# top.net
KiCad netlist of a schematic drawn in Altium Designer
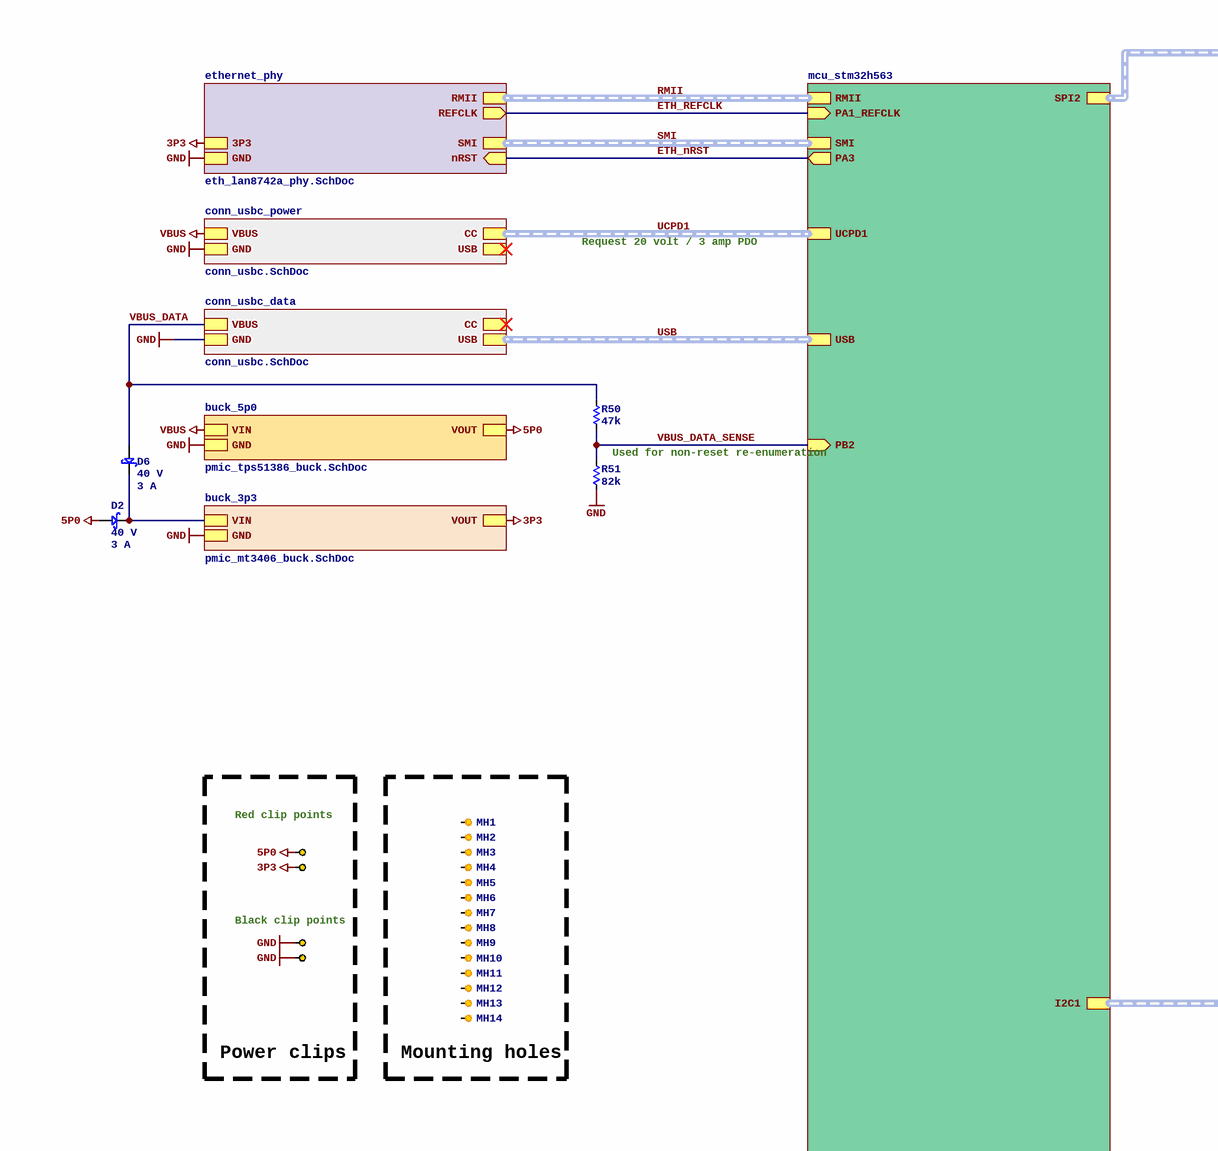
[diagram p0: top.SchDoc, top left]
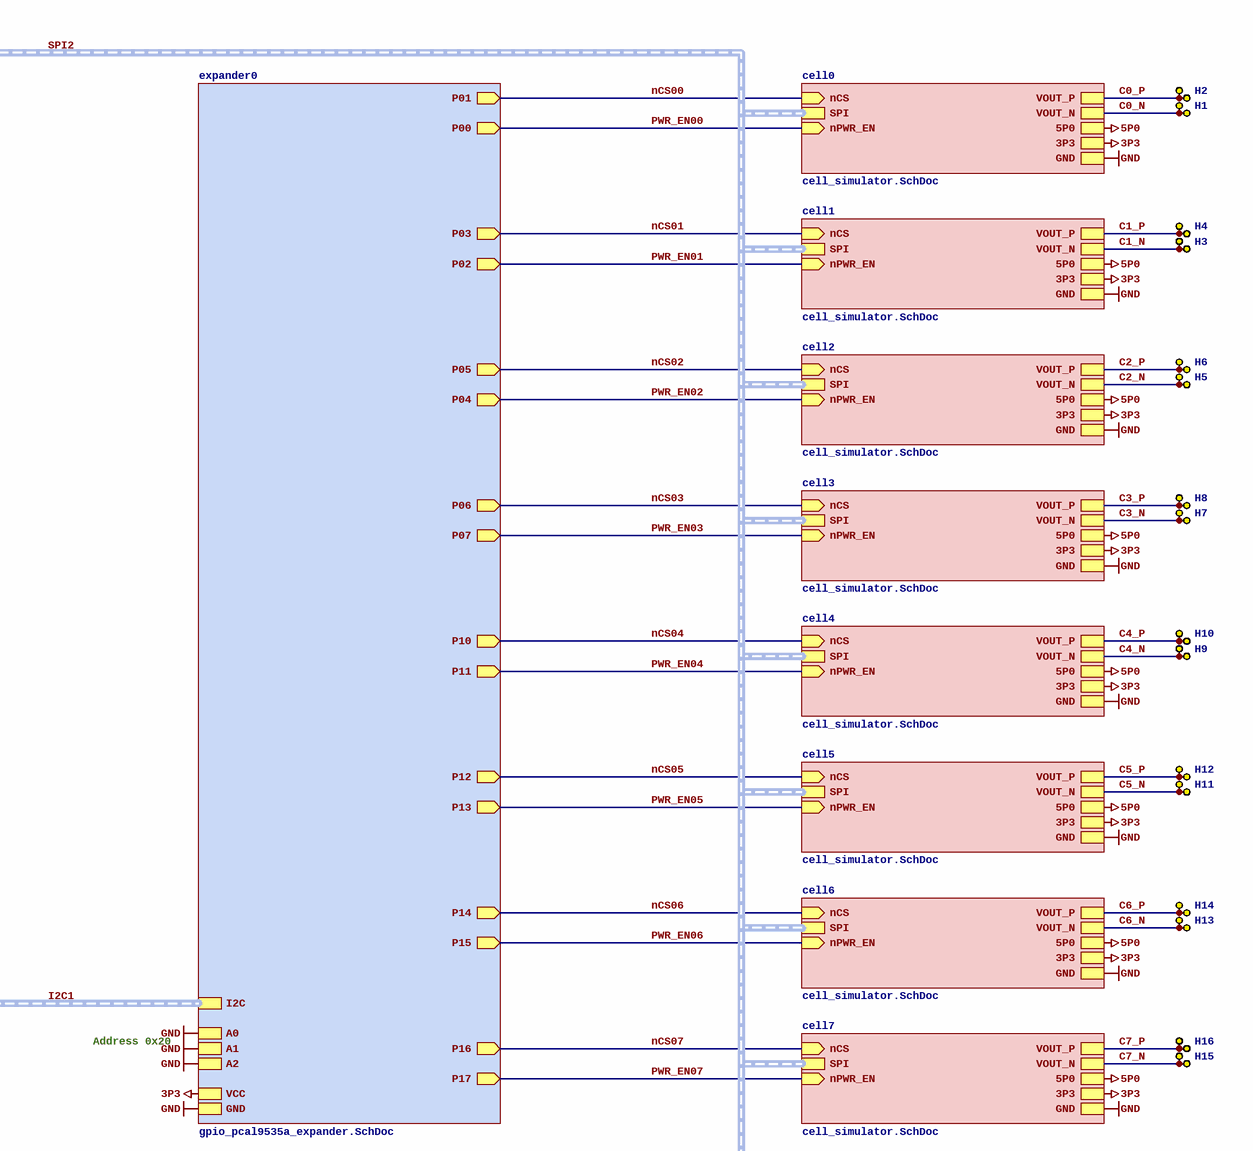
[diagram p1: top.SchDoc, top right]
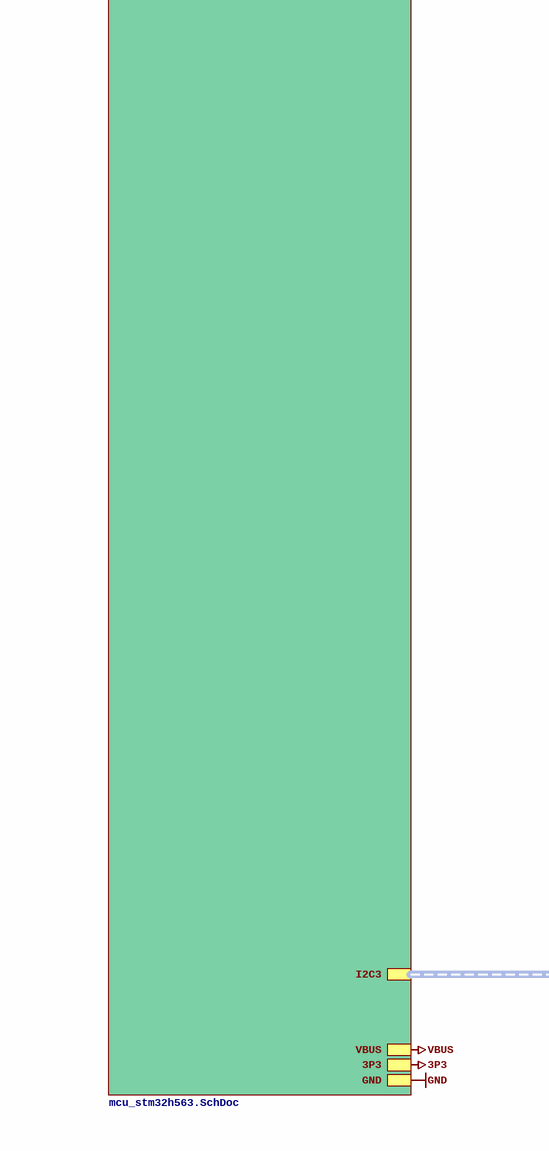
[diagram p2: top.SchDoc, bottom left]
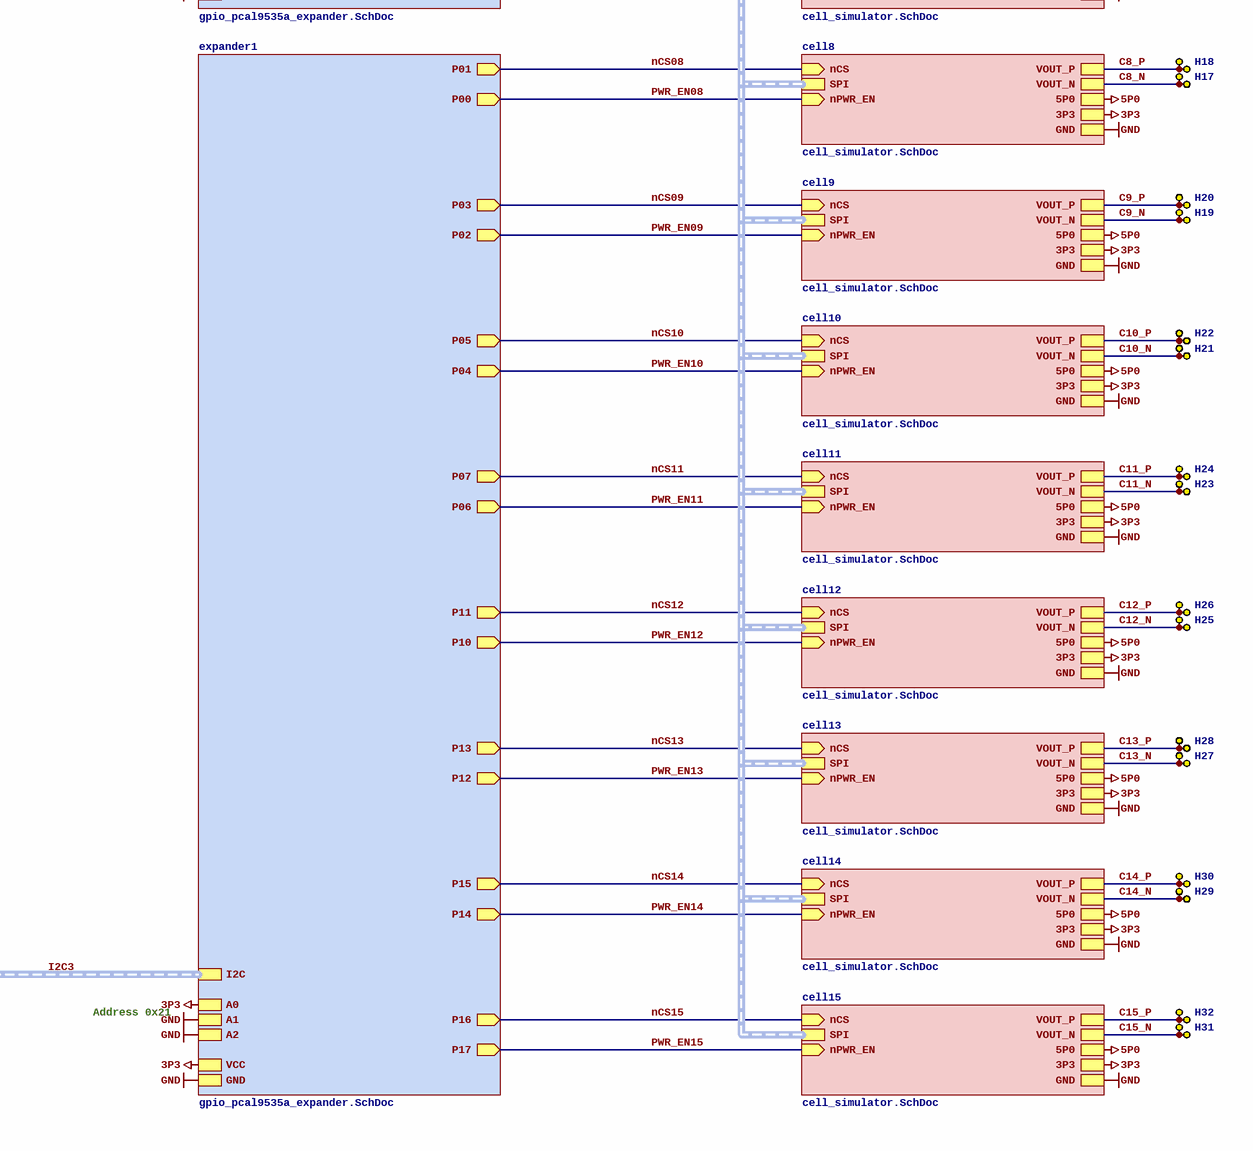
[diagram p3: top.SchDoc, bottom right]

(export (version "E")
  (design (tool "Eeschema 10.0.6"))
  (components
    (comp (ref "D2")
      (value "B340A-13-F")
      (footprint "SMA")
      (description "Rectifier Diode, Schottky, 1 Phase, 1 Element, 3A, 40V V(RRM), Silicon")
      (fields
        (field (name "MANUFACTURER") "Diodes")
        (field (name "VR") "40 V")
        (field (name "CURRENT") "3 A")
      )
      (libsource (lib "database") (part "__template_diode_schottky"))
    )
    (comp (ref "D6")
      (value "B340A-13-F")
      (footprint "SMA")
      (description "Rectifier Diode, Schottky, 1 Phase, 1 Element, 3A, 40V V(RRM), Silicon")
      (fields
        (field (name "MANUFACTURER") "Diodes")
        (field (name "VR") "40 V")
        (field (name "CURRENT") "3 A")
      )
      (libsource (lib "database") (part "__template_diode_schottky"))
    )
    (comp (ref "H1")
      (value "SMTSO20100CTJ")
      (footprint "SINHOO_SMTSO20100CTJ")
      (description "Standoff M2 x 0.4, tin-plated, 10 mm height")
      (fields (field (name "MANUFACTURER") "Sinhoo"))
      (libsource (lib "database") (part "SMTSO20100CTJ"))
    )
    (comp (ref "H2")
      (value "SMTSO20100CTJ")
      (footprint "SINHOO_SMTSO20100CTJ")
      (description "Standoff M2 x 0.4, tin-plated, 10 mm height")
      (fields (field (name "MANUFACTURER") "Sinhoo"))
      (libsource (lib "database") (part "SMTSO20100CTJ"))
    )
    (comp (ref "H3")
      (value "SMTSO20100CTJ")
      (footprint "SINHOO_SMTSO20100CTJ")
      (description "Standoff M2 x 0.4, tin-plated, 10 mm height")
      (fields (field (name "MANUFACTURER") "Sinhoo"))
      (libsource (lib "database") (part "SMTSO20100CTJ"))
    )
    (comp (ref "H4")
      (value "SMTSO20100CTJ")
      (footprint "SINHOO_SMTSO20100CTJ")
      (description "Standoff M2 x 0.4, tin-plated, 10 mm height")
      (fields (field (name "MANUFACTURER") "Sinhoo"))
      (libsource (lib "database") (part "SMTSO20100CTJ"))
    )
    (comp (ref "H5")
      (value "SMTSO20100CTJ")
      (footprint "SINHOO_SMTSO20100CTJ")
      (description "Standoff M2 x 0.4, tin-plated, 10 mm height")
      (fields (field (name "MANUFACTURER") "Sinhoo"))
      (libsource (lib "database") (part "SMTSO20100CTJ"))
    )
    (comp (ref "H6")
      (value "SMTSO20100CTJ")
      (footprint "SINHOO_SMTSO20100CTJ")
      (description "Standoff M2 x 0.4, tin-plated, 10 mm height")
      (fields (field (name "MANUFACTURER") "Sinhoo"))
      (libsource (lib "database") (part "SMTSO20100CTJ"))
    )
    (comp (ref "H7")
      (value "SMTSO20100CTJ")
      (footprint "SINHOO_SMTSO20100CTJ")
      (description "Standoff M2 x 0.4, tin-plated, 10 mm height")
      (fields (field (name "MANUFACTURER") "Sinhoo"))
      (libsource (lib "database") (part "SMTSO20100CTJ"))
    )
    (comp (ref "H8")
      (value "SMTSO20100CTJ")
      (footprint "SINHOO_SMTSO20100CTJ")
      (description "Standoff M2 x 0.4, tin-plated, 10 mm height")
      (fields (field (name "MANUFACTURER") "Sinhoo"))
      (libsource (lib "database") (part "SMTSO20100CTJ"))
    )
    (comp (ref "H9")
      (value "SMTSO20100CTJ")
      (footprint "SINHOO_SMTSO20100CTJ")
      (description "Standoff M2 x 0.4, tin-plated, 10 mm height")
      (fields (field (name "MANUFACTURER") "Sinhoo"))
      (libsource (lib "database") (part "SMTSO20100CTJ"))
    )
    (comp (ref "H10")
      (value "SMTSO20100CTJ")
      (footprint "SINHOO_SMTSO20100CTJ")
      (description "Standoff M2 x 0.4, tin-plated, 10 mm height")
      (fields (field (name "MANUFACTURER") "Sinhoo"))
      (libsource (lib "database") (part "SMTSO20100CTJ"))
    )
    (comp (ref "H11")
      (value "SMTSO20100CTJ")
      (footprint "SINHOO_SMTSO20100CTJ")
      (description "Standoff M2 x 0.4, tin-plated, 10 mm height")
      (fields (field (name "MANUFACTURER") "Sinhoo"))
      (libsource (lib "database") (part "SMTSO20100CTJ"))
    )
    (comp (ref "H12")
      (value "SMTSO20100CTJ")
      (footprint "SINHOO_SMTSO20100CTJ")
      (description "Standoff M2 x 0.4, tin-plated, 10 mm height")
      (fields (field (name "MANUFACTURER") "Sinhoo"))
      (libsource (lib "database") (part "SMTSO20100CTJ"))
    )
    (comp (ref "H13")
      (value "SMTSO20100CTJ")
      (footprint "SINHOO_SMTSO20100CTJ")
      (description "Standoff M2 x 0.4, tin-plated, 10 mm height")
      (fields (field (name "MANUFACTURER") "Sinhoo"))
      (libsource (lib "database") (part "SMTSO20100CTJ"))
    )
    (comp (ref "H14")
      (value "SMTSO20100CTJ")
      (footprint "SINHOO_SMTSO20100CTJ")
      (description "Standoff M2 x 0.4, tin-plated, 10 mm height")
      (fields (field (name "MANUFACTURER") "Sinhoo"))
      (libsource (lib "database") (part "SMTSO20100CTJ"))
    )
    (comp (ref "H15")
      (value "SMTSO20100CTJ")
      (footprint "SINHOO_SMTSO20100CTJ")
      (description "Standoff M2 x 0.4, tin-plated, 10 mm height")
      (fields (field (name "MANUFACTURER") "Sinhoo"))
      (libsource (lib "database") (part "SMTSO20100CTJ"))
    )
    (comp (ref "H16")
      (value "SMTSO20100CTJ")
      (footprint "SINHOO_SMTSO20100CTJ")
      (description "Standoff M2 x 0.4, tin-plated, 10 mm height")
      (fields (field (name "MANUFACTURER") "Sinhoo"))
      (libsource (lib "database") (part "SMTSO20100CTJ"))
    )
    (comp (ref "H17")
      (value "SMTSO20100CTJ")
      (footprint "SINHOO_SMTSO20100CTJ")
      (description "Standoff M2 x 0.4, tin-plated, 10 mm height")
      (fields (field (name "MANUFACTURER") "Sinhoo"))
      (libsource (lib "database") (part "SMTSO20100CTJ"))
    )
    (comp (ref "H18")
      (value "SMTSO20100CTJ")
      (footprint "SINHOO_SMTSO20100CTJ")
      (description "Standoff M2 x 0.4, tin-plated, 10 mm height")
      (fields (field (name "MANUFACTURER") "Sinhoo"))
      (libsource (lib "database") (part "SMTSO20100CTJ"))
    )
    (comp (ref "H19")
      (value "SMTSO20100CTJ")
      (footprint "SINHOO_SMTSO20100CTJ")
      (description "Standoff M2 x 0.4, tin-plated, 10 mm height")
      (fields (field (name "MANUFACTURER") "Sinhoo"))
      (libsource (lib "database") (part "SMTSO20100CTJ"))
    )
    (comp (ref "H20")
      (value "SMTSO20100CTJ")
      (footprint "SINHOO_SMTSO20100CTJ")
      (description "Standoff M2 x 0.4, tin-plated, 10 mm height")
      (fields (field (name "MANUFACTURER") "Sinhoo"))
      (libsource (lib "database") (part "SMTSO20100CTJ"))
    )
    (comp (ref "H21")
      (value "SMTSO20100CTJ")
      (footprint "SINHOO_SMTSO20100CTJ")
      (description "Standoff M2 x 0.4, tin-plated, 10 mm height")
      (fields (field (name "MANUFACTURER") "Sinhoo"))
      (libsource (lib "database") (part "SMTSO20100CTJ"))
    )
    (comp (ref "H22")
      (value "SMTSO20100CTJ")
      (footprint "SINHOO_SMTSO20100CTJ")
      (description "Standoff M2 x 0.4, tin-plated, 10 mm height")
      (fields (field (name "MANUFACTURER") "Sinhoo"))
      (libsource (lib "database") (part "SMTSO20100CTJ"))
    )
    (comp (ref "H23")
      (value "SMTSO20100CTJ")
      (footprint "SINHOO_SMTSO20100CTJ")
      (description "Standoff M2 x 0.4, tin-plated, 10 mm height")
      (fields (field (name "MANUFACTURER") "Sinhoo"))
      (libsource (lib "database") (part "SMTSO20100CTJ"))
    )
    (comp (ref "H24")
      (value "SMTSO20100CTJ")
      (footprint "SINHOO_SMTSO20100CTJ")
      (description "Standoff M2 x 0.4, tin-plated, 10 mm height")
      (fields (field (name "MANUFACTURER") "Sinhoo"))
      (libsource (lib "database") (part "SMTSO20100CTJ"))
    )
    (comp (ref "H25")
      (value "SMTSO20100CTJ")
      (footprint "SINHOO_SMTSO20100CTJ")
      (description "Standoff M2 x 0.4, tin-plated, 10 mm height")
      (fields (field (name "MANUFACTURER") "Sinhoo"))
      (libsource (lib "database") (part "SMTSO20100CTJ"))
    )
    (comp (ref "H26")
      (value "SMTSO20100CTJ")
      (footprint "SINHOO_SMTSO20100CTJ")
      (description "Standoff M2 x 0.4, tin-plated, 10 mm height")
      (fields (field (name "MANUFACTURER") "Sinhoo"))
      (libsource (lib "database") (part "SMTSO20100CTJ"))
    )
    (comp (ref "H27")
      (value "SMTSO20100CTJ")
      (footprint "SINHOO_SMTSO20100CTJ")
      (description "Standoff M2 x 0.4, tin-plated, 10 mm height")
      (fields (field (name "MANUFACTURER") "Sinhoo"))
      (libsource (lib "database") (part "SMTSO20100CTJ"))
    )
    (comp (ref "H28")
      (value "SMTSO20100CTJ")
      (footprint "SINHOO_SMTSO20100CTJ")
      (description "Standoff M2 x 0.4, tin-plated, 10 mm height")
      (fields (field (name "MANUFACTURER") "Sinhoo"))
      (libsource (lib "database") (part "SMTSO20100CTJ"))
    )
    (comp (ref "H29")
      (value "SMTSO20100CTJ")
      (footprint "SINHOO_SMTSO20100CTJ")
      (description "Standoff M2 x 0.4, tin-plated, 10 mm height")
      (fields (field (name "MANUFACTURER") "Sinhoo"))
      (libsource (lib "database") (part "SMTSO20100CTJ"))
    )
    (comp (ref "H30")
      (value "SMTSO20100CTJ")
      (footprint "SINHOO_SMTSO20100CTJ")
      (description "Standoff M2 x 0.4, tin-plated, 10 mm height")
      (fields (field (name "MANUFACTURER") "Sinhoo"))
      (libsource (lib "database") (part "SMTSO20100CTJ"))
    )
    (comp (ref "H31")
      (value "SMTSO20100CTJ")
      (footprint "SINHOO_SMTSO20100CTJ")
      (description "Standoff M2 x 0.4, tin-plated, 10 mm height")
      (fields (field (name "MANUFACTURER") "Sinhoo"))
      (libsource (lib "database") (part "SMTSO20100CTJ"))
    )
    (comp (ref "H32")
      (value "SMTSO20100CTJ")
      (footprint "SINHOO_SMTSO20100CTJ")
      (description "Standoff M2 x 0.4, tin-plated, 10 mm height")
      (fields (field (name "MANUFACTURER") "Sinhoo"))
      (libsource (lib "database") (part "SMTSO20100CTJ"))
    )
    (comp (ref "MH1") (value "HOLE_M3") (footprint "HOLE_M3") (libsource (lib "database") (part "HOLE")))
    (comp (ref "MH2") (value "HOLE_M3") (footprint "HOLE_M3") (libsource (lib "database") (part "HOLE")))
    (comp (ref "MH3") (value "HOLE_M3") (footprint "HOLE_M3") (libsource (lib "database") (part "HOLE")))
    (comp (ref "MH4") (value "HOLE_M3") (footprint "HOLE_M3") (libsource (lib "database") (part "HOLE")))
    (comp (ref "MH5") (value "HOLE_M3") (footprint "HOLE_M3") (libsource (lib "database") (part "HOLE")))
    (comp (ref "MH6") (value "HOLE_M3") (footprint "HOLE_M3") (libsource (lib "database") (part "HOLE")))
    (comp (ref "MH7") (value "HOLE_M3") (footprint "HOLE_M3") (libsource (lib "database") (part "HOLE")))
    (comp (ref "MH8") (value "HOLE_M3") (footprint "HOLE_M3") (libsource (lib "database") (part "HOLE")))
    (comp (ref "MH9") (value "HOLE_M3") (footprint "HOLE_M3") (libsource (lib "database") (part "HOLE")))
    (comp (ref "MH10") (value "HOLE_M3") (footprint "HOLE_M3") (libsource (lib "database") (part "HOLE")))
    (comp (ref "MH11") (value "HOLE_M3") (footprint "HOLE_M3") (libsource (lib "database") (part "HOLE")))
    (comp (ref "MH12") (value "HOLE_M3") (footprint "HOLE_M3") (libsource (lib "database") (part "HOLE")))
    (comp (ref "MH13") (value "HOLE_M3") (footprint "HOLE_M3") (libsource (lib "database") (part "HOLE")))
    (comp (ref "MH14") (value "HOLE_M3") (footprint "HOLE_M3") (libsource (lib "database") (part "HOLE")))
    (comp (ref "R50")
      (value "47k")
      (footprint "R0402")
      (fields
        (field (name "MANUFACTURER PART NUMBER") "0402WGF4702TCE")
        (field (name "MANUFACTURER") "UNI-ROYAL(Uniroyal Elec)")
        (field (name "TOLERANCE") "1%")
      )
      (libsource (lib "database") (part "__template_resistor"))
    )
    (comp (ref "R51")
      (value "82k")
      (footprint "R0402")
      (fields
        (field (name "MANUFACTURER PART NUMBER") "FRC0402F8202TS")
        (field (name "MANUFACTURER") "FOJAN")
        (field (name "TOLERANCE") "1%")
      )
      (libsource (lib "database") (part "__template_resistor"))
    )
    (comp (ref "TP4")
      (value "RH-5000")
      (footprint "TP_RH-5000")
      (description "Red through-hole PCB test point")
      (fields (field (name "MANUFACTURER") "ronghe"))
      (libsource (lib "database") (part "__template_testpoint"))
    )
    (comp (ref "TP5")
      (value "RH-5001")
      (footprint "TP_RH-5001")
      (description "Black through-hole PCB test point")
      (fields (field (name "MANUFACTURER") "ronghe"))
      (libsource (lib "database") (part "__template_testpoint"))
    )
    (comp (ref "TP6")
      (value "RH-5000")
      (footprint "TP_RH-5000")
      (description "Red through-hole PCB test point")
      (fields (field (name "MANUFACTURER") "ronghe"))
      (libsource (lib "database") (part "__template_testpoint"))
    )
    (comp (ref "TP7")
      (value "RH-5001")
      (footprint "TP_RH-5001")
      (description "Black through-hole PCB test point")
      (fields (field (name "MANUFACTURER") "ronghe"))
      (libsource (lib "database") (part "__template_testpoint"))
    )
    (comp (ref "TP8")
      (value "RH-5000")
      (footprint "TP_RH-5000")
      (description "Red through-hole PCB test point")
      (fields (field (name "MANUFACTURER") "ronghe"))
      (libsource (lib "database") (part "__template_testpoint"))
    )
    (comp (ref "TP9")
      (value "RH-5001")
      (footprint "TP_RH-5001")
      (description "Black through-hole PCB test point")
      (fields (field (name "MANUFACTURER") "ronghe"))
      (libsource (lib "database") (part "__template_testpoint"))
    )
    (comp (ref "TP10")
      (value "RH-5000")
      (footprint "TP_RH-5000")
      (description "Red through-hole PCB test point")
      (fields (field (name "MANUFACTURER") "ronghe"))
      (libsource (lib "database") (part "__template_testpoint"))
    )
    (comp (ref "TP11")
      (value "RH-5001")
      (footprint "TP_RH-5001")
      (description "Black through-hole PCB test point")
      (fields (field (name "MANUFACTURER") "ronghe"))
      (libsource (lib "database") (part "__template_testpoint"))
    )
    (comp (ref "TP12")
      (value "RH-5000")
      (footprint "TP_RH-5000")
      (description "Red through-hole PCB test point")
      (fields (field (name "MANUFACTURER") "ronghe"))
      (libsource (lib "database") (part "__template_testpoint"))
    )
    (comp (ref "TP13")
      (value "RH-5001")
      (footprint "TP_RH-5001")
      (description "Black through-hole PCB test point")
      (fields (field (name "MANUFACTURER") "ronghe"))
      (libsource (lib "database") (part "__template_testpoint"))
    )
    (comp (ref "TP14")
      (value "RH-5000")
      (footprint "TP_RH-5000")
      (description "Red through-hole PCB test point")
      (fields (field (name "MANUFACTURER") "ronghe"))
      (libsource (lib "database") (part "__template_testpoint"))
    )
    (comp (ref "TP15")
      (value "RH-5001")
      (footprint "TP_RH-5001")
      (description "Black through-hole PCB test point")
      (fields (field (name "MANUFACTURER") "ronghe"))
      (libsource (lib "database") (part "__template_testpoint"))
    )
    (comp (ref "TP16")
      (value "RH-5000")
      (footprint "TP_RH-5000")
      (description "Red through-hole PCB test point")
      (fields (field (name "MANUFACTURER") "ronghe"))
      (libsource (lib "database") (part "__template_testpoint"))
    )
    (comp (ref "TP17")
      (value "RH-5001")
      (footprint "TP_RH-5001")
      (description "Black through-hole PCB test point")
      (fields (field (name "MANUFACTURER") "ronghe"))
      (libsource (lib "database") (part "__template_testpoint"))
    )
    (comp (ref "TP18")
      (value "RH-5000")
      (footprint "TP_RH-5000")
      (description "Red through-hole PCB test point")
      (fields (field (name "MANUFACTURER") "ronghe"))
      (libsource (lib "database") (part "__template_testpoint"))
    )
    (comp (ref "TP19")
      (value "RH-5001")
      (footprint "TP_RH-5001")
      (description "Black through-hole PCB test point")
      (fields (field (name "MANUFACTURER") "ronghe"))
      (libsource (lib "database") (part "__template_testpoint"))
    )
    (comp (ref "TP20")
      (value "RH-5000")
      (footprint "TP_RH-5000")
      (description "Red through-hole PCB test point")
      (fields (field (name "MANUFACTURER") "ronghe"))
      (libsource (lib "database") (part "__template_testpoint"))
    )
    (comp (ref "TP21")
      (value "RH-5001")
      (footprint "TP_RH-5001")
      (description "Black through-hole PCB test point")
      (fields (field (name "MANUFACTURER") "ronghe"))
      (libsource (lib "database") (part "__template_testpoint"))
    )
    (comp (ref "TP22")
      (value "RH-5000")
      (footprint "TP_RH-5000")
      (description "Red through-hole PCB test point")
      (fields (field (name "MANUFACTURER") "ronghe"))
      (libsource (lib "database") (part "__template_testpoint"))
    )
    (comp (ref "TP23")
      (value "RH-5001")
      (footprint "TP_RH-5001")
      (description "Black through-hole PCB test point")
      (fields (field (name "MANUFACTURER") "ronghe"))
      (libsource (lib "database") (part "__template_testpoint"))
    )
    (comp (ref "TP24")
      (value "RH-5000")
      (footprint "TP_RH-5000")
      (description "Red through-hole PCB test point")
      (fields (field (name "MANUFACTURER") "ronghe"))
      (libsource (lib "database") (part "__template_testpoint"))
    )
    (comp (ref "TP25")
      (value "RH-5001")
      (footprint "TP_RH-5001")
      (description "Black through-hole PCB test point")
      (fields (field (name "MANUFACTURER") "ronghe"))
      (libsource (lib "database") (part "__template_testpoint"))
    )
    (comp (ref "TP26")
      (value "RH-5000")
      (footprint "TP_RH-5000")
      (description "Red through-hole PCB test point")
      (fields (field (name "MANUFACTURER") "ronghe"))
      (libsource (lib "database") (part "__template_testpoint"))
    )
    (comp (ref "TP27")
      (value "RH-5001")
      (footprint "TP_RH-5001")
      (description "Black through-hole PCB test point")
      (fields (field (name "MANUFACTURER") "ronghe"))
      (libsource (lib "database") (part "__template_testpoint"))
    )
    (comp (ref "TP28")
      (value "RH-5000")
      (footprint "TP_RH-5000")
      (description "Red through-hole PCB test point")
      (fields (field (name "MANUFACTURER") "ronghe"))
      (libsource (lib "database") (part "__template_testpoint"))
    )
    (comp (ref "TP29")
      (value "RH-5001")
      (footprint "TP_RH-5001")
      (description "Black through-hole PCB test point")
      (fields (field (name "MANUFACTURER") "ronghe"))
      (libsource (lib "database") (part "__template_testpoint"))
    )
    (comp (ref "TP30")
      (value "RH-5000")
      (footprint "TP_RH-5000")
      (description "Red through-hole PCB test point")
      (fields (field (name "MANUFACTURER") "ronghe"))
      (libsource (lib "database") (part "__template_testpoint"))
    )
    (comp (ref "TP31")
      (value "RH-5001")
      (footprint "TP_RH-5001")
      (description "Black through-hole PCB test point")
      (fields (field (name "MANUFACTURER") "ronghe"))
      (libsource (lib "database") (part "__template_testpoint"))
    )
    (comp (ref "TP32")
      (value "RH-5000")
      (footprint "TP_RH-5000")
      (description "Red through-hole PCB test point")
      (fields (field (name "MANUFACTURER") "ronghe"))
      (libsource (lib "database") (part "__template_testpoint"))
    )
    (comp (ref "TP33")
      (value "RH-5000")
      (footprint "TP_RH-5000")
      (description "Red through-hole PCB test point")
      (fields (field (name "MANUFACTURER") "ronghe"))
      (libsource (lib "database") (part "__template_testpoint"))
    )
    (comp (ref "TP34")
      (value "RH-5001")
      (footprint "TP_RH-5001")
      (description "Black through-hole PCB test point")
      (fields (field (name "MANUFACTURER") "ronghe"))
      (libsource (lib "database") (part "__template_testpoint"))
    )
    (comp (ref "TP35")
      (value "RH-5000")
      (footprint "TP_RH-5000")
      (description "Red through-hole PCB test point")
      (fields (field (name "MANUFACTURER") "ronghe"))
      (libsource (lib "database") (part "__template_testpoint"))
    )
    (comp (ref "TP36")
      (value "RH-5000")
      (footprint "TP_RH-5000")
      (description "Red through-hole PCB test point")
      (fields (field (name "MANUFACTURER") "ronghe"))
      (libsource (lib "database") (part "__template_testpoint"))
    )
    (comp (ref "TP38")
      (value "RH-5001")
      (footprint "TP_RH-5001")
      (description "Black through-hole PCB test point")
      (fields (field (name "MANUFACTURER") "ronghe"))
      (libsource (lib "database") (part "__template_testpoint"))
    )
    (comp (ref "TP39")
      (value "RH-5001")
      (footprint "TP_RH-5001")
      (description "Black through-hole PCB test point")
      (fields (field (name "MANUFACTURER") "ronghe"))
      (libsource (lib "database") (part "__template_testpoint"))
    )
    (comp (ref "TP43")
      (value "RH-5001")
      (footprint "TP_RH-5001")
      (description "Black through-hole PCB test point")
      (fields (field (name "MANUFACTURER") "ronghe"))
      (libsource (lib "database") (part "__template_testpoint"))
    )
  )
  (nets
    (net (code "8") (name "/C0_N") (class "Default")
      (node (ref "H1") (pin "1") (pintype "passive"))
      (node (ref "TP5") (pin "1") (pintype "passive"))
    )
    (net (code "9") (name "/C0_P") (class "Default")
      (node (ref "H2") (pin "1") (pintype "passive"))
      (node (ref "TP4") (pin "1") (pintype "passive"))
    )
    (net (code "10") (name "/C1_N") (class "Default")
      (node (ref "H3") (pin "1") (pintype "passive"))
      (node (ref "TP7") (pin "1") (pintype "passive"))
    )
    (net (code "11") (name "/C1_P") (class "Default")
      (node (ref "H4") (pin "1") (pintype "passive"))
      (node (ref "TP6") (pin "1") (pintype "passive"))
    )
    (net (code "12") (name "/C2_N") (class "Default")
      (node (ref "H5") (pin "1") (pintype "passive"))
      (node (ref "TP9") (pin "1") (pintype "passive"))
    )
    (net (code "13") (name "/C2_P") (class "Default")
      (node (ref "H6") (pin "1") (pintype "passive"))
      (node (ref "TP8") (pin "1") (pintype "passive"))
    )
    (net (code "14") (name "/C3_N") (class "Default")
      (node (ref "H7") (pin "1") (pintype "passive"))
      (node (ref "TP11") (pin "1") (pintype "passive"))
    )
    (net (code "15") (name "/C3_P") (class "Default")
      (node (ref "H8") (pin "1") (pintype "passive"))
      (node (ref "TP10") (pin "1") (pintype "passive"))
    )
    (net (code "16") (name "/C4_N") (class "Default")
      (node (ref "H9") (pin "1") (pintype "passive"))
      (node (ref "TP13") (pin "1") (pintype "passive"))
    )
    (net (code "17") (name "/C4_P") (class "Default")
      (node (ref "H10") (pin "1") (pintype "passive"))
      (node (ref "TP12") (pin "1") (pintype "passive"))
    )
    (net (code "18") (name "/C5_N") (class "Default")
      (node (ref "H11") (pin "1") (pintype "passive"))
      (node (ref "TP15") (pin "1") (pintype "passive"))
    )
    (net (code "19") (name "/C5_P") (class "Default")
      (node (ref "H12") (pin "1") (pintype "passive"))
      (node (ref "TP14") (pin "1") (pintype "passive"))
    )
    (net (code "20") (name "/C6_N") (class "Default")
      (node (ref "H13") (pin "1") (pintype "passive"))
      (node (ref "TP17") (pin "1") (pintype "passive"))
    )
    (net (code "21") (name "/C6_P") (class "Default")
      (node (ref "H14") (pin "1") (pintype "passive"))
      (node (ref "TP16") (pin "1") (pintype "passive"))
    )
    (net (code "22") (name "/C7_N") (class "Default")
      (node (ref "H15") (pin "1") (pintype "passive"))
      (node (ref "TP19") (pin "1") (pintype "passive"))
    )
    (net (code "23") (name "/C7_P") (class "Default")
      (node (ref "H16") (pin "1") (pintype "passive"))
      (node (ref "TP18") (pin "1") (pintype "passive"))
    )
    (net (code "24") (name "/C8_N") (class "Default")
      (node (ref "H17") (pin "1") (pintype "passive"))
      (node (ref "TP21") (pin "1") (pintype "passive"))
    )
    (net (code "25") (name "/C8_P") (class "Default")
      (node (ref "H18") (pin "1") (pintype "passive"))
      (node (ref "TP20") (pin "1") (pintype "passive"))
    )
    (net (code "26") (name "/C9_N") (class "Default")
      (node (ref "H19") (pin "1") (pintype "passive"))
      (node (ref "TP23") (pin "1") (pintype "passive"))
    )
    (net (code "27") (name "/C9_P") (class "Default")
      (node (ref "H20") (pin "1") (pintype "passive"))
      (node (ref "TP22") (pin "1") (pintype "passive"))
    )
    (net (code "28") (name "/C10_N") (class "Default")
      (node (ref "H21") (pin "1") (pintype "passive"))
      (node (ref "TP25") (pin "1") (pintype "passive"))
    )
    (net (code "29") (name "/C10_P") (class "Default")
      (node (ref "H22") (pin "1") (pintype "passive"))
      (node (ref "TP24") (pin "1") (pintype "passive"))
    )
    (net (code "30") (name "/C11_N") (class "Default")
      (node (ref "H23") (pin "1") (pintype "passive"))
      (node (ref "TP27") (pin "1") (pintype "passive"))
    )
    (net (code "31") (name "/C11_P") (class "Default")
      (node (ref "H24") (pin "1") (pintype "passive"))
      (node (ref "TP26") (pin "1") (pintype "passive"))
    )
    (net (code "32") (name "/C12_N") (class "Default")
      (node (ref "H25") (pin "1") (pintype "passive"))
      (node (ref "TP29") (pin "1") (pintype "passive"))
    )
    (net (code "33") (name "/C12_P") (class "Default")
      (node (ref "H26") (pin "1") (pintype "passive"))
      (node (ref "TP28") (pin "1") (pintype "passive"))
    )
    (net (code "34") (name "/C13_N") (class "Default")
      (node (ref "H27") (pin "1") (pintype "passive"))
      (node (ref "TP31") (pin "1") (pintype "passive"))
    )
    (net (code "35") (name "/C13_P") (class "Default")
      (node (ref "H28") (pin "1") (pintype "passive"))
      (node (ref "TP30") (pin "1") (pintype "passive"))
    )
    (net (code "36") (name "/C14_N") (class "Default")
      (node (ref "H29") (pin "1") (pintype "passive"))
      (node (ref "TP34") (pin "1") (pintype "passive"))
    )
    (net (code "37") (name "/C14_P") (class "Default")
      (node (ref "H30") (pin "1") (pintype "passive"))
      (node (ref "TP32") (pin "1") (pintype "passive"))
    )
    (net (code "38") (name "/C15_N") (class "Default")
      (node (ref "H31") (pin "1") (pintype "passive"))
      (node (ref "TP38") (pin "1") (pintype "passive"))
    )
    (net (code "39") (name "/C15_P") (class "Default")
      (node (ref "H32") (pin "1") (pintype "passive"))
      (node (ref "TP36") (pin "1") (pintype "passive"))
    )
    (net (code "60") (name "/VBUS_DATA") (class "Default")
      (node (ref "D6") (pin "1") (pintype "passive"))
      (node (ref "R50") (pin "2") (pintype "passive"))
    )
    (net (code "61") (name "/VBUS_DATA_SENSE") (class "Default")
      (node (ref "R50") (pin "1") (pintype "passive"))
      (node (ref "R51") (pin "2") (pintype "passive"))
    )
    (net (code "62") (name "/VIN") (class "Default")
      (node (ref "D2") (pin "2") (pintype "passive"))
      (node (ref "D6") (pin "2") (pintype "passive"))
    )
    (net (code "86") (name "3P3") (class "Default") (node (ref "TP35") (pin "1") (pintype "passive")))
    (net (code "87") (name "5P0") (class "Default")
      (node (ref "D2") (pin "1") (pintype "passive"))
      (node (ref "TP33") (pin "1") (pintype "passive"))
    )
    (net (code "88") (name "GND") (class "Default")
      (node (ref "R51") (pin "1") (pintype "passive"))
      (node (ref "TP39") (pin "1") (pintype "passive"))
      (node (ref "TP43") (pin "1") (pintype "passive"))
    )
    (net (code "90") (name "unconnected-(MH1-Pad1)") (class "Default")
      (node (ref "MH1") (pin "1") (pintype "passive"))
    )
    (net (code "91") (name "unconnected-(MH2-Pad1)") (class "Default")
      (node (ref "MH2") (pin "1") (pintype "passive"))
    )
    (net (code "92") (name "unconnected-(MH3-Pad1)") (class "Default")
      (node (ref "MH3") (pin "1") (pintype "passive"))
    )
    (net (code "93") (name "unconnected-(MH4-Pad1)") (class "Default")
      (node (ref "MH4") (pin "1") (pintype "passive"))
    )
    (net (code "94") (name "unconnected-(MH5-Pad1)") (class "Default")
      (node (ref "MH5") (pin "1") (pintype "passive"))
    )
    (net (code "95") (name "unconnected-(MH6-Pad1)") (class "Default")
      (node (ref "MH6") (pin "1") (pintype "passive"))
    )
    (net (code "96") (name "unconnected-(MH7-Pad1)") (class "Default")
      (node (ref "MH7") (pin "1") (pintype "passive"))
    )
    (net (code "97") (name "unconnected-(MH8-Pad1)") (class "Default")
      (node (ref "MH8") (pin "1") (pintype "passive"))
    )
    (net (code "98") (name "unconnected-(MH9-Pad1)") (class "Default")
      (node (ref "MH9") (pin "1") (pintype "passive"))
    )
    (net (code "99") (name "unconnected-(MH10-Pad1)") (class "Default")
      (node (ref "MH10") (pin "1") (pintype "passive"))
    )
    (net (code "100") (name "unconnected-(MH11-Pad1)") (class "Default")
      (node (ref "MH11") (pin "1") (pintype "passive"))
    )
    (net (code "101") (name "unconnected-(MH12-Pad1)") (class "Default")
      (node (ref "MH12") (pin "1") (pintype "passive"))
    )
    (net (code "102") (name "unconnected-(MH13-Pad1)") (class "Default")
      (node (ref "MH13") (pin "1") (pintype "passive"))
    )
    (net (code "103") (name "unconnected-(MH14-Pad1)") (class "Default")
      (node (ref "MH14") (pin "1") (pintype "passive"))
    )
  )
)
